# Board_2_sensor_v1.net
KiCad netlist of a schematic drawn in EAGLE
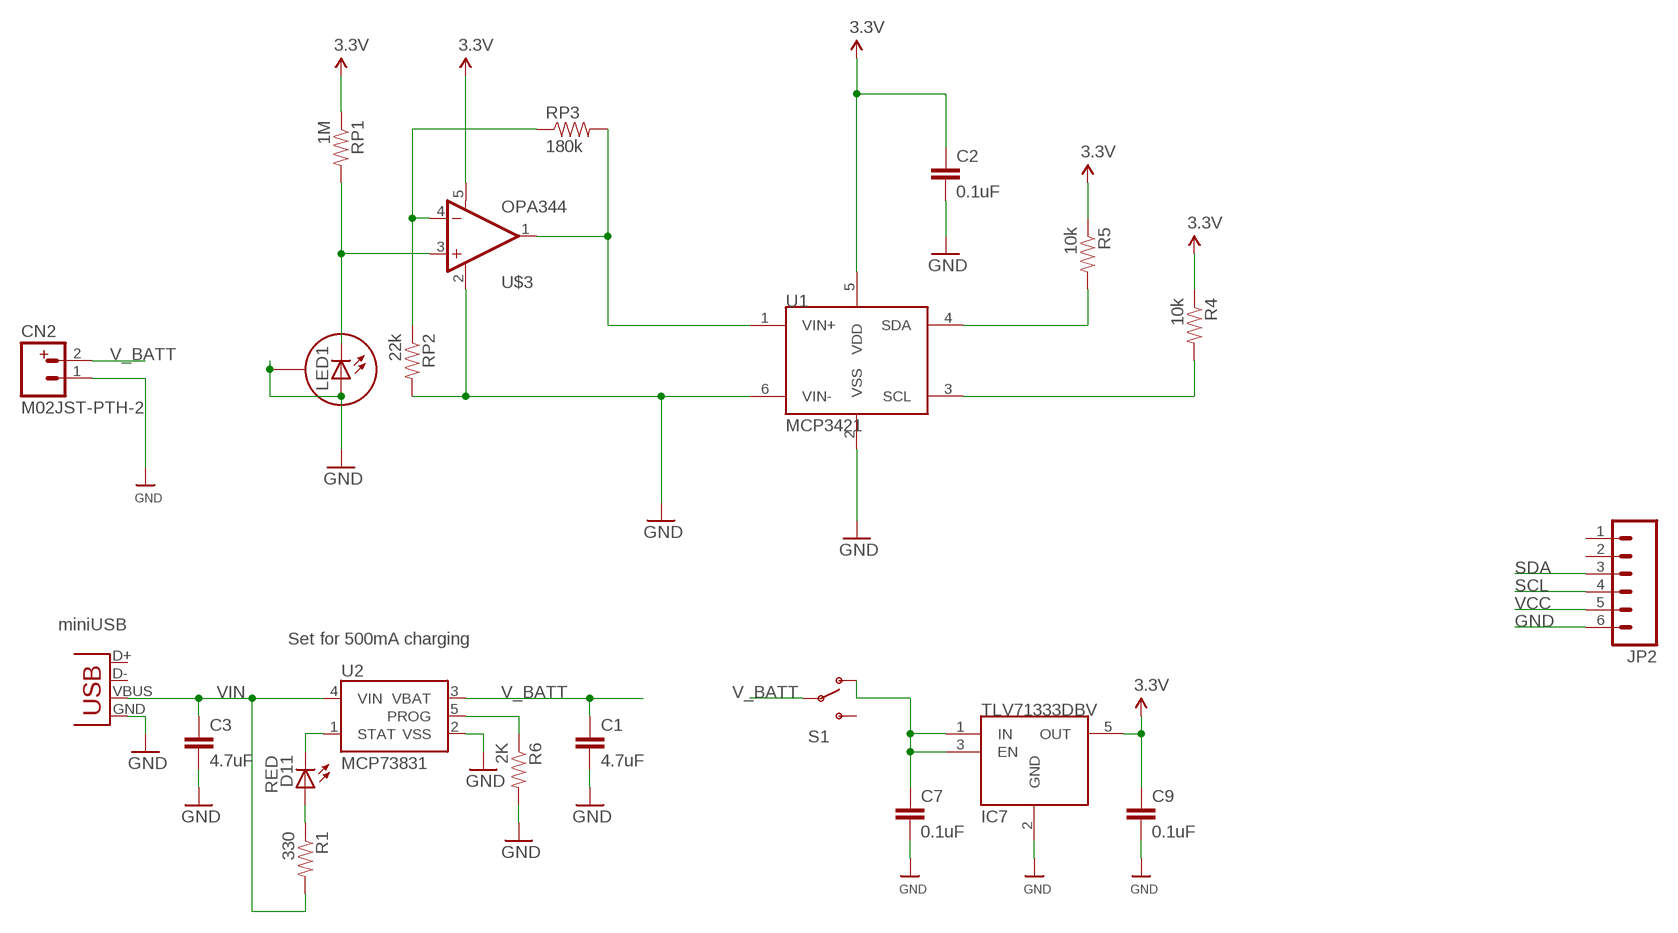
[diagram p0: schematic, sheet 1]

(export (version "E")
  (design (tool "Eeschema 10.0.6"))
  (components
    (comp (ref "C1")
      (value "4.7uF")
      (footprint "eagle-import:0402-CAP")
      (libsource (lib "eagle-import") (part "CAP0402-CAP"))
    )
    (comp (ref "C2")
      (value "0.1uF")
      (footprint "eagle-import:0402-CAP")
      (libsource (lib "eagle-import") (part "CAP0402-CAP"))
    )
    (comp (ref "C3")
      (value "4.7uF")
      (footprint "eagle-import:0402-CAP")
      (libsource (lib "eagle-import") (part "CAP0402-CAP"))
    )
    (comp (ref "C7")
      (value "0.1uF")
      (footprint "eagle-import:C0402")
      (libsource (lib "eagle-import") (part "C-EUC0402"))
    )
    (comp (ref "C9")
      (value "0.1uF")
      (footprint "eagle-import:C0402")
      (libsource (lib "eagle-import") (part "C-EUC0402"))
    )
    (comp (ref "CN2")
      (value "M02JST-PTH-2")
      (footprint "eagle-import:JST-2-PTH")
      (libsource (lib "eagle-import") (part "M02JST-PTH-2"))
    )
    (comp (ref "D11")
      (value "RED")
      (footprint "eagle-import:LED-0603")
      (libsource (lib "eagle-import") (part "LED0603"))
    )
    (comp (ref "IC7")
      (value "TLV71333DBV")
      (footprint "eagle-import:SOT-23-5")
      (libsource (lib "eagle-import") (part "TLV713DBV33"))
    )
    (comp (ref "JP2")
      (value "M06SMD-1MM")
      (footprint "eagle-import:1X06-1MM")
      (libsource (lib "eagle-import") (part "M06SMD-1MM"))
    )
    (comp (ref "LED1")
      (value "MTPD1346")
      (footprint "eagle-import:TO-46")
      (libsource (lib "eagle-import") (part "MTPD1346"))
    )
    (comp (ref "R1")
      (value "330")
      (footprint "eagle-import:0402-RES")
      (libsource (lib "eagle-import") (part "RESISTOR0402-RES"))
    )
    (comp (ref "R4")
      (value "10k")
      (footprint "eagle-import:0402-RES")
      (libsource (lib "eagle-import") (part "RESISTOR0402-RES"))
    )
    (comp (ref "R5")
      (value "10k")
      (footprint "eagle-import:0402-RES")
      (libsource (lib "eagle-import") (part "RESISTOR0402-RES"))
    )
    (comp (ref "R6")
      (value "2K")
      (footprint "eagle-import:0402-RES")
      (libsource (lib "eagle-import") (part "RESISTOR0402-RES"))
    )
    (comp (ref "RP1")
      (value "1M")
      (footprint "eagle-import:0402-RES")
      (libsource (lib "eagle-import") (part "RESISTOR0402-RES"))
    )
    (comp (ref "RP2")
      (value "22k")
      (footprint "eagle-import:0402-RES")
      (libsource (lib "eagle-import") (part "RESISTOR0402-RES"))
    )
    (comp (ref "RP3")
      (value "180k")
      (footprint "eagle-import:0402-RES")
      (libsource (lib "eagle-import") (part "RESISTOR0402-RES"))
    )
    (comp (ref "S1")
      (value "SWITCH-SPDTSMD")
      (footprint "eagle-import:AYZ0202")
      (libsource (lib "eagle-import") (part "SWITCH-SPDTSMD"))
    )
    (comp (ref "U$3")
      (value "OPA344")
      (footprint "eagle-import:SOT23-5")
      (libsource (lib "eagle-import") (part "OPA344"))
    )
    (comp (ref "U1")
      (value "MCP3421")
      (footprint "eagle-import:SOT-23-6")
      (libsource (lib "eagle-import") (part "MCP3421"))
    )
    (comp (ref "U2")
      (value "MCP73831")
      (footprint "eagle-import:SOT23-5")
      (libsource (lib "eagle-import") (part "MCP73831"))
    )
    (comp (ref "X1")
      (value "Micro USB")
      (footprint "eagle-import:USB-MICROB")
      (libsource (lib "eagle-import") (part "USB-MICROB"))
    )
  )
  (nets
    (net (code "1") (name "/SCL") (class "Default")
      (node (ref "JP2") (pin "4") (pinfunction "4_4") (pintype "passive"))
      (node (ref "R4") (pin "2") (pinfunction "2_2") (pintype "passive"))
      (node (ref "U1") (pin "3") (pinfunction "SCL_3") (pintype "bidirectional"))
    )
    (net (code "2") (name "/SDA") (class "Default")
      (node (ref "JP2") (pin "3") (pinfunction "3_3") (pintype "passive"))
      (node (ref "R5") (pin "2") (pinfunction "2_2") (pintype "passive"))
      (node (ref "U1") (pin "4") (pinfunction "SDA_4") (pintype "bidirectional"))
    )
    (net (code "3") (name "/VIN") (class "Default")
      (node (ref "C3") (pin "1") (pinfunction "1_1") (pintype "passive"))
      (node (ref "R1") (pin "2") (pinfunction "2_2") (pintype "passive"))
      (node (ref "U2") (pin "4") (pinfunction "VIN_4") (pintype "power_in"))
      (node (ref "X1") (pin "VBUS") (pinfunction "VBUS_VBUS") (pintype "bidirectional"))
    )
    (net (code "4") (name "/V_BATT") (class "Default")
      (node (ref "C1") (pin "1") (pinfunction "1_1") (pintype "passive"))
      (node (ref "CN2") (pin "2") (pinfunction "2_2") (pintype "passive"))
      (node (ref "S1") (pin "2") (pinfunction "P_2") (pintype "passive"))
      (node (ref "U2") (pin "3") (pinfunction "VBAT_3") (pintype "power_in"))
    )
    (net (code "5") (name "3.3V") (class "Default")
      (node (ref "C2") (pin "1") (pinfunction "1_1") (pintype "passive"))
      (node (ref "C9") (pin "1") (pinfunction "1_1") (pintype "passive"))
      (node (ref "IC7") (pin "5") (pinfunction "OUT_5") (pintype "power_in"))
      (node (ref "JP2") (pin "5") (pinfunction "5_5") (pintype "passive"))
      (node (ref "R4") (pin "1") (pinfunction "1_1") (pintype "passive"))
      (node (ref "R5") (pin "1") (pinfunction "1_1") (pintype "passive"))
      (node (ref "RP1") (pin "1") (pinfunction "1_1") (pintype "passive"))
      (node (ref "U$3") (pin "5") (pinfunction "V+_5") (pintype "power_in"))
      (node (ref "U1") (pin "5") (pinfunction "VDD_5") (pintype "bidirectional"))
    )
    (net (code "6") (name "GND") (class "Default")
      (node (ref "C1") (pin "2") (pinfunction "2_2") (pintype "passive"))
      (node (ref "C2") (pin "2") (pinfunction "2_2") (pintype "passive"))
      (node (ref "C3") (pin "2") (pinfunction "2_2") (pintype "passive"))
      (node (ref "C7") (pin "2") (pinfunction "2_2") (pintype "passive"))
      (node (ref "C9") (pin "2") (pinfunction "2_2") (pintype "passive"))
      (node (ref "CN2") (pin "1") (pinfunction "1_1") (pintype "passive"))
      (node (ref "IC7") (pin "2") (pinfunction "GND_2") (pintype "power_in"))
      (node (ref "JP2") (pin "6") (pinfunction "6_6") (pintype "passive"))
      (node (ref "LED1") (pin "C") (pinfunction "C_C") (pintype "passive"))
      (node (ref "LED1") (pin "CASE") (pinfunction "CASE_CASE") (pintype "bidirectional"))
      (node (ref "R6") (pin "2") (pinfunction "2_2") (pintype "passive"))
      (node (ref "RP2") (pin "2") (pinfunction "2_2") (pintype "passive"))
      (node (ref "U$3") (pin "2") (pinfunction "V-_2") (pintype "power_in"))
      (node (ref "U1") (pin "2") (pinfunction "VSS_2") (pintype "bidirectional"))
      (node (ref "U1") (pin "6") (pinfunction "VIN-_6") (pintype "bidirectional"))
      (node (ref "U2") (pin "2") (pinfunction "VSS_2") (pintype "power_in"))
      (node (ref "X1") (pin "GND") (pinfunction "GND_GND") (pintype "bidirectional"))
    )
    (net (code "7") (name "Net-(D11-PadA)") (class "Default")
      (node (ref "D11") (pin "A") (pinfunction "A_A") (pintype "passive"))
      (node (ref "R1") (pin "1") (pinfunction "1_1") (pintype "passive"))
    )
    (net (code "8") (name "Net-(IC7-EN)") (class "Default")
      (node (ref "C7") (pin "1") (pinfunction "1_1") (pintype "passive"))
      (node (ref "IC7") (pin "1") (pinfunction "IN_1") (pintype "power_in"))
      (node (ref "IC7") (pin "3") (pinfunction "EN_3") (pintype "input"))
      (node (ref "S1") (pin "1") (pinfunction "O_1") (pintype "passive"))
    )
    (net (code "9") (name "Net-(U$3-+IN)") (class "Default")
      (node (ref "LED1") (pin "A") (pinfunction "A_A") (pintype "passive"))
      (node (ref "RP1") (pin "2") (pinfunction "2_2") (pintype "passive"))
      (node (ref "U$3") (pin "3") (pinfunction "+IN_3") (pintype "input"))
    )
    (net (code "10") (name "Net-(U$3--IN)") (class "Default")
      (node (ref "RP2") (pin "1") (pinfunction "1_1") (pintype "passive"))
      (node (ref "RP3") (pin "1") (pinfunction "1_1") (pintype "passive"))
      (node (ref "U$3") (pin "4") (pinfunction "-IN_4") (pintype "input"))
    )
    (net (code "11") (name "Net-(U$3-OUT)") (class "Default")
      (node (ref "RP3") (pin "2") (pinfunction "2_2") (pintype "passive"))
      (node (ref "U$3") (pin "1") (pinfunction "OUT_1") (pintype "output"))
      (node (ref "U1") (pin "1") (pinfunction "VIN+_1") (pintype "bidirectional"))
    )
    (net (code "12") (name "Net-(U2-PROG)") (class "Default")
      (node (ref "R6") (pin "1") (pinfunction "1_1") (pintype "passive"))
      (node (ref "U2") (pin "5") (pinfunction "PROG_5") (pintype "input"))
    )
    (net (code "13") (name "Net-(U2-STAT)") (class "Default")
      (node (ref "D11") (pin "C") (pinfunction "C_C") (pintype "passive"))
      (node (ref "U2") (pin "1") (pinfunction "STAT_1") (pintype "output"))
    )
    (net (code "14") (name "unconnected-(JP2-Pad1)") (class "Default")
      (node (ref "JP2") (pin "1") (pinfunction "1_1") (pintype "passive"))
    )
    (net (code "15") (name "unconnected-(JP2-Pad2)") (class "Default")
      (node (ref "JP2") (pin "2") (pinfunction "2_2") (pintype "passive"))
    )
    (net (code "16") (name "unconnected-(S1-S-Pad3)") (class "Default")
      (node (ref "S1") (pin "3") (pinfunction "S_3") (pintype "passive"))
    )
    (net (code "17") (name "unconnected-(X1-PadD+)") (class "Default")
      (node (ref "X1") (pin "D+") (pinfunction "D+_D+") (pintype "bidirectional"))
    )
    (net (code "18") (name "unconnected-(X1-PadD-)") (class "Default")
      (node (ref "X1") (pin "D-") (pinfunction "D-_D-") (pintype "bidirectional"))
    )
  )
)
